# rpicam.net
KiCad netlist of a schematic drawn in EAGLE
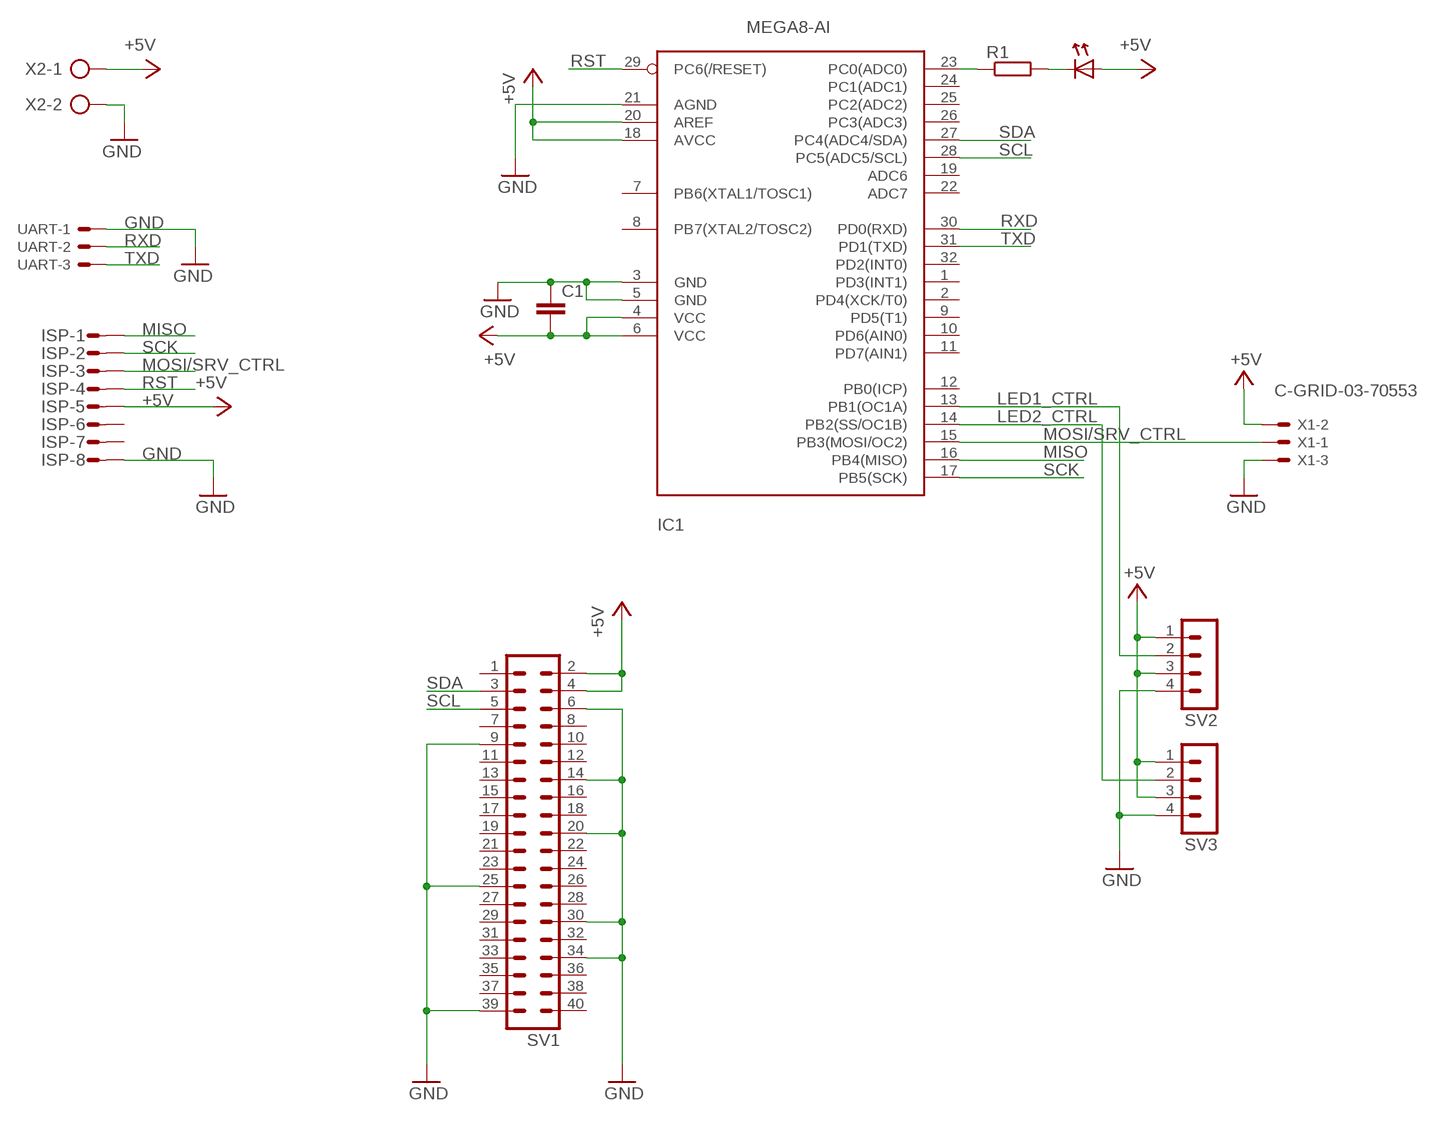
[diagram p0: schematic, sheet 1]

(export (version "E")
  (design (tool "Eeschema 10.0.6"))
  (components
    (comp (ref "C1")
      (value "C-EUC0603")
      (footprint "eagle-import:C0603")
      (libsource (lib "eagle-import") (part "C-EUC0603"))
    )
    (comp (ref "IC1")
      (value "MEGA8-AI")
      (footprint "eagle-import:TQFP32-08")
      (libsource (lib "eagle-import") (part "MEGA8-AI"))
    )
    (comp (ref "ISP")
      (value "MICROMATCH-8")
      (footprint "eagle-import:MICROMATCH-8")
      (fields (field (name "MF") "FARNELL") (field (name "MPN") "7-215464-8"))
      (libsource (lib "eagle-import") (part "MICROMATCH-8"))
    )
    (comp (ref "R1")
      (value "R-EU_R0603")
      (footprint "eagle-import:R0603")
      (libsource (lib "eagle-import") (part "R-EU_R0603"))
    )
    (comp (ref "SV1")
      (value "MA20-2")
      (footprint "eagle-import:MA20-2")
      (libsource (lib "eagle-import") (part "MA20-2"))
    )
    (comp (ref "SV2")
      (value "MA04-1")
      (footprint "eagle-import:MA04-1")
      (libsource (lib "eagle-import") (part "MA04-1"))
    )
    (comp (ref "SV3")
      (value "MA04-1")
      (footprint "eagle-import:MA04-1")
      (libsource (lib "eagle-import") (part "MA04-1"))
    )
    (comp (ref "U$1")
      (value "LED0603")
      (footprint "eagle-import:D0603")
      (libsource (lib "eagle-import") (part "LED0603"))
    )
    (comp (ref "UART")
      (value "uart")
      (footprint "eagle-import:70553-03")
      (libsource (lib "eagle-import") (part "C-GRID-03-70553"))
    )
    (comp (ref "X1")
      (value "C-GRID-03-70553")
      (footprint "eagle-import:70553-03")
      (libsource (lib "eagle-import") (part "C-GRID-03-70553"))
    )
    (comp (ref "X2")
      (value "AK500/2")
      (footprint "eagle-import:AK500_2")
      (libsource (lib "eagle-import") (part "AK500/2"))
    )
  )
  (nets
    (net (code "1") (name "+5V") (class "Default")
      (node (ref "C1") (pin "2") (pinfunction "2_2") (pintype "passive"))
      (node (ref "IC1") (pin "18") (pinfunction "AVCC_18") (pintype "power_in"))
      (node (ref "IC1") (pin "20") (pinfunction "AREF_20") (pintype "passive"))
      (node (ref "IC1") (pin "4") (pinfunction "VCC_4") (pintype "power_in"))
      (node (ref "IC1") (pin "6") (pinfunction "VCC_6") (pintype "power_in"))
      (node (ref "ISP") (pin "5") (pinfunction "S_5") (pintype "passive"))
      (node (ref "SV1") (pin "2") (pinfunction "2_2") (pintype "passive"))
      (node (ref "SV1") (pin "4") (pinfunction "4_4") (pintype "passive"))
      (node (ref "SV2") (pin "1") (pinfunction "1_1") (pintype "passive"))
      (node (ref "SV2") (pin "3") (pinfunction "3_3") (pintype "passive"))
      (node (ref "SV3") (pin "1") (pinfunction "1_1") (pintype "passive"))
      (node (ref "SV3") (pin "3") (pinfunction "3_3") (pintype "passive"))
      (node (ref "U$1") (pin "1") (pinfunction "A_1") (pintype "passive"))
      (node (ref "X1") (pin "2") (pinfunction "S_2") (pintype "passive"))
      (node (ref "X2") (pin "1") (pinfunction "KL_1") (pintype "passive"))
    )
    (net (code "2") (name "/LED1_CTRL") (class "Default")
      (node (ref "IC1") (pin "13") (pinfunction "PB1(OC1A)_13") (pintype "bidirectional"))
      (node (ref "SV2") (pin "2") (pinfunction "2_2") (pintype "passive"))
    )
    (net (code "3") (name "/LED2_CTRL") (class "Default")
      (node (ref "IC1") (pin "14") (pinfunction "PB2(SS/OC1B)_14") (pintype "bidirectional"))
      (node (ref "SV3") (pin "2") (pinfunction "2_2") (pintype "passive"))
    )
    (net (code "4") (name "/MISO") (class "Default")
      (node (ref "IC1") (pin "16") (pinfunction "PB4(MISO)_16") (pintype "bidirectional"))
      (node (ref "ISP") (pin "1") (pinfunction "S_1") (pintype "passive"))
    )
    (net (code "5") (name "/MOSI{slash}SRV_CTRL") (class "Default")
      (node (ref "IC1") (pin "15") (pinfunction "PB3(MOSI/OC2)_15") (pintype "bidirectional"))
      (node (ref "ISP") (pin "3") (pinfunction "S_3") (pintype "passive"))
      (node (ref "X1") (pin "1") (pinfunction "S_1") (pintype "passive"))
    )
    (net (code "6") (name "/RST") (class "Default")
      (node (ref "IC1") (pin "29") (pinfunction "PC6(/RESET)_29") (pintype "bidirectional"))
      (node (ref "ISP") (pin "4") (pinfunction "S_4") (pintype "passive"))
    )
    (net (code "7") (name "/RXD") (class "Default")
      (node (ref "IC1") (pin "30") (pinfunction "PD0(RXD)_30") (pintype "bidirectional"))
      (node (ref "UART") (pin "2") (pinfunction "S_2") (pintype "passive"))
    )
    (net (code "8") (name "/SCK") (class "Default")
      (node (ref "IC1") (pin "17") (pinfunction "PB5(SCK)_17") (pintype "bidirectional"))
      (node (ref "ISP") (pin "2") (pinfunction "S_2") (pintype "passive"))
    )
    (net (code "9") (name "/SCL") (class "Default")
      (node (ref "IC1") (pin "28") (pinfunction "PC5(ADC5/SCL)_28") (pintype "bidirectional"))
      (node (ref "SV1") (pin "5") (pinfunction "5_5") (pintype "passive"))
    )
    (net (code "10") (name "/SDA") (class "Default")
      (node (ref "IC1") (pin "27") (pinfunction "PC4(ADC4/SDA)_27") (pintype "bidirectional"))
      (node (ref "SV1") (pin "3") (pinfunction "3_3") (pintype "passive"))
    )
    (net (code "11") (name "/TXD") (class "Default")
      (node (ref "IC1") (pin "31") (pinfunction "PD1(TXD)_31") (pintype "bidirectional"))
      (node (ref "UART") (pin "3") (pinfunction "S_3") (pintype "passive"))
    )
    (net (code "12") (name "GND") (class "Default")
      (node (ref "C1") (pin "1") (pinfunction "1_1") (pintype "passive"))
      (node (ref "IC1") (pin "21") (pinfunction "AGND_21") (pintype "power_in"))
      (node (ref "IC1") (pin "3") (pinfunction "GND_3") (pintype "power_in"))
      (node (ref "IC1") (pin "5") (pinfunction "GND_5") (pintype "power_in"))
      (node (ref "ISP") (pin "8") (pinfunction "S_8") (pintype "passive"))
      (node (ref "SV1") (pin "14") (pinfunction "14_14") (pintype "passive"))
      (node (ref "SV1") (pin "20") (pinfunction "20_20") (pintype "passive"))
      (node (ref "SV1") (pin "25") (pinfunction "25_25") (pintype "passive"))
      (node (ref "SV1") (pin "30") (pinfunction "30_30") (pintype "passive"))
      (node (ref "SV1") (pin "34") (pinfunction "34_34") (pintype "passive"))
      (node (ref "SV1") (pin "39") (pinfunction "39_39") (pintype "passive"))
      (node (ref "SV1") (pin "6") (pinfunction "6_6") (pintype "passive"))
      (node (ref "SV1") (pin "9") (pinfunction "9_9") (pintype "passive"))
      (node (ref "SV2") (pin "4") (pinfunction "4_4") (pintype "passive"))
      (node (ref "SV3") (pin "4") (pinfunction "4_4") (pintype "passive"))
      (node (ref "UART") (pin "1") (pinfunction "S_1") (pintype "passive"))
      (node (ref "X1") (pin "3") (pinfunction "S_3") (pintype "passive"))
      (node (ref "X2") (pin "2") (pinfunction "KL_2") (pintype "passive"))
    )
    (net (code "13") (name "Net-(IC1-PC0(ADC0))") (class "Default")
      (node (ref "IC1") (pin "23") (pinfunction "PC0(ADC0)_23") (pintype "bidirectional"))
      (node (ref "R1") (pin "1") (pinfunction "1_1") (pintype "passive"))
    )
    (net (code "14") (name "Net-(U$1-C)") (class "Default")
      (node (ref "R1") (pin "2") (pinfunction "2_2") (pintype "passive"))
      (node (ref "U$1") (pin "2") (pinfunction "C_2") (pintype "passive"))
    )
    (net (code "15") (name "unconnected-(IC1-ADC6-Pad19)") (class "Default")
      (node (ref "IC1") (pin "19") (pinfunction "ADC6_19") (pintype "bidirectional"))
    )
    (net (code "16") (name "unconnected-(IC1-ADC7-Pad22)") (class "Default")
      (node (ref "IC1") (pin "22") (pinfunction "ADC7_22") (pintype "bidirectional"))
    )
    (net (code "17") (name "unconnected-(IC1-PB0(ICP)-Pad12)") (class "Default")
      (node (ref "IC1") (pin "12") (pinfunction "PB0(ICP)_12") (pintype "bidirectional"))
    )
    (net (code "18") (name "unconnected-(IC1-PB6(XTAL1{slash}TOSC1)-Pad7)") (class "Default")
      (node (ref "IC1") (pin "7") (pinfunction "PB6(XTAL1/TOSC1)_7") (pintype "bidirectional"))
    )
    (net (code "19") (name "unconnected-(IC1-PB7(XTAL2{slash}TOSC2)-Pad8)") (class "Default")
      (node (ref "IC1") (pin "8") (pinfunction "PB7(XTAL2/TOSC2)_8") (pintype "bidirectional"))
    )
    (net (code "20") (name "unconnected-(IC1-PC1(ADC1)-Pad24)") (class "Default")
      (node (ref "IC1") (pin "24") (pinfunction "PC1(ADC1)_24") (pintype "bidirectional"))
    )
    (net (code "21") (name "unconnected-(IC1-PC2(ADC2)-Pad25)") (class "Default")
      (node (ref "IC1") (pin "25") (pinfunction "PC2(ADC2)_25") (pintype "bidirectional"))
    )
    (net (code "22") (name "unconnected-(IC1-PC3(ADC3)-Pad26)") (class "Default")
      (node (ref "IC1") (pin "26") (pinfunction "PC3(ADC3)_26") (pintype "bidirectional"))
    )
    (net (code "23") (name "unconnected-(IC1-PD2(INT0)-Pad32)") (class "Default")
      (node (ref "IC1") (pin "32") (pinfunction "PD2(INT0)_32") (pintype "bidirectional"))
    )
    (net (code "24") (name "unconnected-(IC1-PD3(INT1)-Pad1)") (class "Default")
      (node (ref "IC1") (pin "1") (pinfunction "PD3(INT1)_1") (pintype "bidirectional"))
    )
    (net (code "25") (name "unconnected-(IC1-PD4(XCK{slash}T0)-Pad2)") (class "Default")
      (node (ref "IC1") (pin "2") (pinfunction "PD4(XCK/T0)_2") (pintype "bidirectional"))
    )
    (net (code "26") (name "unconnected-(IC1-PD5(T1)-Pad9)") (class "Default")
      (node (ref "IC1") (pin "9") (pinfunction "PD5(T1)_9") (pintype "bidirectional"))
    )
    (net (code "27") (name "unconnected-(IC1-PD6(AIN0)-Pad10)") (class "Default")
      (node (ref "IC1") (pin "10") (pinfunction "PD6(AIN0)_10") (pintype "bidirectional"))
    )
    (net (code "28") (name "unconnected-(IC1-PD7(AIN1)-Pad11)") (class "Default")
      (node (ref "IC1") (pin "11") (pinfunction "PD7(AIN1)_11") (pintype "bidirectional"))
    )
    (net (code "29") (name "unconnected-(ISPF-S-Pad6)") (class "Default")
      (node (ref "ISP") (pin "6") (pinfunction "S_6") (pintype "passive"))
    )
    (net (code "30") (name "unconnected-(ISPG-S-Pad7)") (class "Default")
      (node (ref "ISP") (pin "7") (pinfunction "S_7") (pintype "passive"))
    )
    (net (code "31") (name "unconnected-(SV1-Pad1)") (class "Default")
      (node (ref "SV1") (pin "1") (pinfunction "1_1") (pintype "passive"))
    )
    (net (code "32") (name "unconnected-(SV1-Pad7)") (class "Default")
      (node (ref "SV1") (pin "7") (pinfunction "7_7") (pintype "passive"))
    )
    (net (code "33") (name "unconnected-(SV1-Pad8)") (class "Default")
      (node (ref "SV1") (pin "8") (pinfunction "8_8") (pintype "passive"))
    )
    (net (code "34") (name "unconnected-(SV1-Pad10)") (class "Default")
      (node (ref "SV1") (pin "10") (pinfunction "10_10") (pintype "passive"))
    )
    (net (code "35") (name "unconnected-(SV1-Pad11)") (class "Default")
      (node (ref "SV1") (pin "11") (pinfunction "11_11") (pintype "passive"))
    )
    (net (code "36") (name "unconnected-(SV1-Pad12)") (class "Default")
      (node (ref "SV1") (pin "12") (pinfunction "12_12") (pintype "passive"))
    )
    (net (code "37") (name "unconnected-(SV1-Pad13)") (class "Default")
      (node (ref "SV1") (pin "13") (pinfunction "13_13") (pintype "passive"))
    )
    (net (code "38") (name "unconnected-(SV1-Pad15)") (class "Default")
      (node (ref "SV1") (pin "15") (pinfunction "15_15") (pintype "passive"))
    )
    (net (code "39") (name "unconnected-(SV1-Pad16)") (class "Default")
      (node (ref "SV1") (pin "16") (pinfunction "16_16") (pintype "passive"))
    )
    (net (code "40") (name "unconnected-(SV1-Pad17)") (class "Default")
      (node (ref "SV1") (pin "17") (pinfunction "17_17") (pintype "passive"))
    )
    (net (code "41") (name "unconnected-(SV1-Pad18)") (class "Default")
      (node (ref "SV1") (pin "18") (pinfunction "18_18") (pintype "passive"))
    )
    (net (code "42") (name "unconnected-(SV1-Pad19)") (class "Default")
      (node (ref "SV1") (pin "19") (pinfunction "19_19") (pintype "passive"))
    )
    (net (code "43") (name "unconnected-(SV1-Pad21)") (class "Default")
      (node (ref "SV1") (pin "21") (pinfunction "21_21") (pintype "passive"))
    )
    (net (code "44") (name "unconnected-(SV1-Pad22)") (class "Default")
      (node (ref "SV1") (pin "22") (pinfunction "22_22") (pintype "passive"))
    )
    (net (code "45") (name "unconnected-(SV1-Pad23)") (class "Default")
      (node (ref "SV1") (pin "23") (pinfunction "23_23") (pintype "passive"))
    )
    (net (code "46") (name "unconnected-(SV1-Pad24)") (class "Default")
      (node (ref "SV1") (pin "24") (pinfunction "24_24") (pintype "passive"))
    )
    (net (code "47") (name "unconnected-(SV1-Pad26)") (class "Default")
      (node (ref "SV1") (pin "26") (pinfunction "26_26") (pintype "passive"))
    )
    (net (code "48") (name "unconnected-(SV1-Pad27)") (class "Default")
      (node (ref "SV1") (pin "27") (pinfunction "27_27") (pintype "passive"))
    )
    (net (code "49") (name "unconnected-(SV1-Pad28)") (class "Default")
      (node (ref "SV1") (pin "28") (pinfunction "28_28") (pintype "passive"))
    )
    (net (code "50") (name "unconnected-(SV1-Pad29)") (class "Default")
      (node (ref "SV1") (pin "29") (pinfunction "29_29") (pintype "passive"))
    )
    (net (code "51") (name "unconnected-(SV1-Pad31)") (class "Default")
      (node (ref "SV1") (pin "31") (pinfunction "31_31") (pintype "passive"))
    )
    (net (code "52") (name "unconnected-(SV1-Pad32)") (class "Default")
      (node (ref "SV1") (pin "32") (pinfunction "32_32") (pintype "passive"))
    )
    (net (code "53") (name "unconnected-(SV1-Pad33)") (class "Default")
      (node (ref "SV1") (pin "33") (pinfunction "33_33") (pintype "passive"))
    )
    (net (code "54") (name "unconnected-(SV1-Pad35)") (class "Default")
      (node (ref "SV1") (pin "35") (pinfunction "35_35") (pintype "passive"))
    )
    (net (code "55") (name "unconnected-(SV1-Pad36)") (class "Default")
      (node (ref "SV1") (pin "36") (pinfunction "36_36") (pintype "passive"))
    )
    (net (code "56") (name "unconnected-(SV1-Pad37)") (class "Default")
      (node (ref "SV1") (pin "37") (pinfunction "37_37") (pintype "passive"))
    )
    (net (code "57") (name "unconnected-(SV1-Pad38)") (class "Default")
      (node (ref "SV1") (pin "38") (pinfunction "38_38") (pintype "passive"))
    )
    (net (code "58") (name "unconnected-(SV1-Pad40)") (class "Default")
      (node (ref "SV1") (pin "40") (pinfunction "40_40") (pintype "passive"))
    )
  )
)
